# OnOff.net
KiCad netlist of a schematic drawn in EAGLE
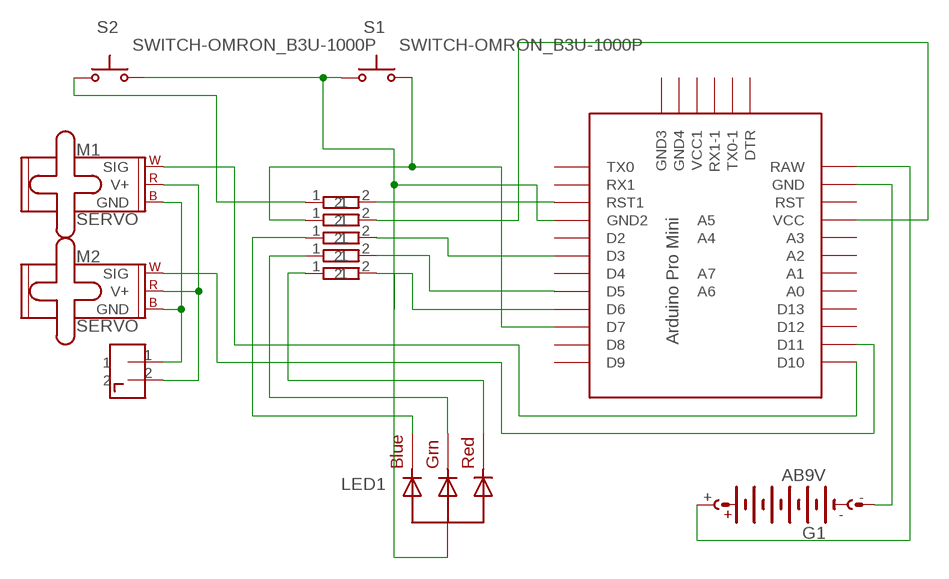
[diagram p0: schematic, sheet 1]

(export (version "E")
  (design (tool "Eeschema 10.0.6"))
  (components
    (comp (ref "CONNECTOR1")
      (value "2PIN")
      (footprint "eagle-import:2PIN")
      (libsource (lib "eagle-import") (part "2PIN"))
    )
    (comp (ref "CONNECTOR2")
      (value "RESISTER")
      (footprint "eagle-import:RESISTER_SOCKET")
      (libsource (lib "eagle-import") (part "RESISTER"))
    )
    (comp (ref "CONNECTOR3")
      (value "RESISTER")
      (footprint "eagle-import:RESISTER_SOCKET")
      (libsource (lib "eagle-import") (part "RESISTER"))
    )
    (comp (ref "CONNECTOR4")
      (value "RESISTER")
      (footprint "eagle-import:RESISTER_SOCKET")
      (libsource (lib "eagle-import") (part "RESISTER"))
    )
    (comp (ref "CONNECTOR5")
      (value "RESISTER")
      (footprint "eagle-import:RESISTER_SOCKET")
      (libsource (lib "eagle-import") (part "RESISTER"))
    )
    (comp (ref "CONNECTOR6")
      (value "RESISTER")
      (footprint "eagle-import:RESISTER_SOCKET")
      (libsource (lib "eagle-import") (part "RESISTER"))
    )
    (comp (ref "G1")
      (value "AB9V")
      (footprint "eagle-import:AB9V")
      (libsource (lib "eagle-import") (part "AB9V"))
    )
    (comp (ref "LED1")
      (value "RGBLED_CA-5MM")
      (footprint "eagle-import:LED5MMRGB")
      (libsource (lib "eagle-import") (part "RGBLED_CA-5MM"))
    )
    (comp (ref "M1")
      (value "SERVO")
      (footprint "eagle-import:1X03")
      (libsource (lib "eagle-import") (part "SERVO"))
    )
    (comp (ref "M2")
      (value "SERVO")
      (footprint "eagle-import:1X03")
      (libsource (lib "eagle-import") (part "SERVO"))
    )
    (comp (ref "S1")
      (value "SWITCH-OMRON_B3U-1000P")
      (footprint "eagle-import:SWITCH-OMRON_B3U-1000P")
      (libsource (lib "eagle-import") (part "SWITCH-OMRON_B3U-1000P"))
    )
    (comp (ref "S2")
      (value "SWITCH-OMRON_B3U-1000P")
      (footprint "eagle-import:SWITCH-OMRON_B3U-1000P")
      (libsource (lib "eagle-import") (part "SWITCH-OMRON_B3U-1000P"))
    )
    (comp (ref "U$1")
      (value "PRO-MINI-2")
      (footprint "eagle-import:PRO-MINI-2")
      (libsource (lib "eagle-import") (part "PRO-MINI-2"))
    )
  )
  (nets
    (net (code "1") (name "Net-(CONNECTOR2-Pad2)") (class "Default")
      (node (ref "CONNECTOR2") (pin "2") (pinfunction "2_2") (pintype "bidirectional"))
      (node (ref "U$1") (pin "RST1") (pinfunction "RST1_RST1") (pintype "bidirectional"))
    )
    (net (code "2") (name "Net-(CONNECTOR3-Pad2)") (class "Default")
      (node (ref "CONNECTOR3") (pin "2") (pinfunction "2_2") (pintype "bidirectional"))
      (node (ref "U$1") (pin "VCC") (pinfunction "VCC_VCC") (pintype "bidirectional"))
    )
    (net (code "3") (name "Net-(CONNECTOR4-Pad2)") (class "Default")
      (node (ref "CONNECTOR4") (pin "2") (pinfunction "2_2") (pintype "bidirectional"))
      (node (ref "U$1") (pin "D3") (pinfunction "D3_D3") (pintype "bidirectional"))
    )
    (net (code "4") (name "Net-(CONNECTOR5-Pad2)") (class "Default")
      (node (ref "CONNECTOR5") (pin "2") (pinfunction "2_2") (pintype "bidirectional"))
      (node (ref "U$1") (pin "D5") (pinfunction "D5_D5") (pintype "bidirectional"))
    )
    (net (code "5") (name "Net-(CONNECTOR6-Pad2)") (class "Default")
      (node (ref "CONNECTOR6") (pin "2") (pinfunction "2_2") (pintype "bidirectional"))
      (node (ref "U$1") (pin "D6") (pinfunction "D6_D6") (pintype "bidirectional"))
    )
    (net (code "6") (name "Net-(G1-Pad+)") (class "Default")
      (node (ref "G1") (pin "+") (pinfunction "+_+") (pintype "passive"))
      (node (ref "U$1") (pin "RAW") (pinfunction "RAW_RAW") (pintype "bidirectional"))
    )
    (net (code "7") (name "Net-(G1-Pad-)") (class "Default")
      (node (ref "G1") (pin "-") (pinfunction "-_-") (pintype "passive"))
      (node (ref "U$1") (pin "GND") (pinfunction "GND_GND") (pintype "bidirectional"))
    )
    (net (code "8") (name "Net-(LED1-BLUE)") (class "Default")
      (node (ref "CONNECTOR4") (pin "1") (pinfunction "1_1") (pintype "bidirectional"))
      (node (ref "LED1") (pin "4") (pinfunction "BLUE_4") (pintype "bidirectional"))
    )
    (net (code "9") (name "Net-(LED1-GREEN)") (class "Default")
      (node (ref "CONNECTOR5") (pin "1") (pinfunction "1_1") (pintype "bidirectional"))
      (node (ref "LED1") (pin "3") (pinfunction "GREEN_3") (pintype "bidirectional"))
    )
    (net (code "10") (name "Net-(LED1-RED)") (class "Default")
      (node (ref "CONNECTOR6") (pin "1") (pinfunction "1_1") (pintype "bidirectional"))
      (node (ref "LED1") (pin "1") (pinfunction "RED_1") (pintype "bidirectional"))
    )
    (net (code "11") (name "Net-(LED1-VCC)") (class "Default")
      (node (ref "LED1") (pin "2") (pinfunction "VCC_2") (pintype "bidirectional"))
      (node (ref "S1") (pin "1") (pinfunction "P_1") (pintype "passive"))
      (node (ref "S2") (pin "2") (pinfunction "S_2") (pintype "passive"))
      (node (ref "U$1") (pin "GND1") (pinfunction "GND2_GND1") (pintype "bidirectional"))
    )
    (net (code "12") (name "Net-(M1-GND)") (class "Default")
      (node (ref "CONNECTOR1") (pin "1") (pinfunction "1_1") (pintype "bidirectional"))
      (node (ref "M1") (pin "3") (pinfunction "GND_3") (pintype "bidirectional"))
      (node (ref "M2") (pin "3") (pinfunction "GND_3") (pintype "bidirectional"))
    )
    (net (code "13") (name "Net-(M1-SIG)") (class "Default")
      (node (ref "M1") (pin "1") (pinfunction "SIG_1") (pintype "bidirectional"))
      (node (ref "U$1") (pin "D10") (pinfunction "D10_D10") (pintype "bidirectional"))
    )
    (net (code "14") (name "Net-(M1-V+)") (class "Default")
      (node (ref "CONNECTOR1") (pin "2") (pinfunction "2_2") (pintype "bidirectional"))
      (node (ref "M1") (pin "2") (pinfunction "V+_2") (pintype "bidirectional"))
      (node (ref "M2") (pin "2") (pinfunction "V+_2") (pintype "bidirectional"))
    )
    (net (code "15") (name "Net-(M2-SIG)") (class "Default")
      (node (ref "M2") (pin "1") (pinfunction "SIG_1") (pintype "bidirectional"))
      (node (ref "U$1") (pin "D11") (pinfunction "D11_D11") (pintype "bidirectional"))
    )
    (net (code "16") (name "Net-(S1-S)") (class "Default")
      (node (ref "CONNECTOR3") (pin "1") (pinfunction "1_1") (pintype "bidirectional"))
      (node (ref "S1") (pin "2") (pinfunction "S_2") (pintype "passive"))
      (node (ref "U$1") (pin "D7") (pinfunction "D7_D7") (pintype "bidirectional"))
    )
    (net (code "17") (name "Net-(S2-P)") (class "Default")
      (node (ref "CONNECTOR2") (pin "1") (pinfunction "1_1") (pintype "bidirectional"))
      (node (ref "S2") (pin "1") (pinfunction "P_1") (pintype "passive"))
    )
    (net (code "18") (name "unconnected-(U$1-GND3-PadGND2)") (class "Default")
      (node (ref "U$1") (pin "GND2") (pinfunction "GND3_GND2") (pintype "bidirectional"))
    )
    (net (code "19") (name "unconnected-(U$1-GND4-PadGND3)") (class "Default")
      (node (ref "U$1") (pin "GND3") (pinfunction "GND4_GND3") (pintype "bidirectional"))
    )
    (net (code "20") (name "unconnected-(U$1-PadA0)") (class "Default")
      (node (ref "U$1") (pin "A0") (pinfunction "A0_A0") (pintype "bidirectional"))
    )
    (net (code "21") (name "unconnected-(U$1-PadA1)") (class "Default")
      (node (ref "U$1") (pin "A1") (pinfunction "A1_A1") (pintype "bidirectional"))
    )
    (net (code "22") (name "unconnected-(U$1-PadA2)") (class "Default")
      (node (ref "U$1") (pin "A2") (pinfunction "A2_A2") (pintype "bidirectional"))
    )
    (net (code "23") (name "unconnected-(U$1-PadA3)") (class "Default")
      (node (ref "U$1") (pin "A3") (pinfunction "A3_A3") (pintype "bidirectional"))
    )
    (net (code "24") (name "unconnected-(U$1-PadA4)") (class "Default")
      (node (ref "U$1") (pin "A4") (pinfunction "A4_A4") (pintype "bidirectional"))
    )
    (net (code "25") (name "unconnected-(U$1-PadA5)") (class "Default")
      (node (ref "U$1") (pin "A5") (pinfunction "A5_A5") (pintype "bidirectional"))
    )
    (net (code "26") (name "unconnected-(U$1-PadA6)") (class "Default")
      (node (ref "U$1") (pin "A6") (pinfunction "A6_A6") (pintype "bidirectional"))
    )
    (net (code "27") (name "unconnected-(U$1-PadA7)") (class "Default")
      (node (ref "U$1") (pin "A7") (pinfunction "A7_A7") (pintype "bidirectional"))
    )
    (net (code "28") (name "unconnected-(U$1-PadD2)") (class "Default")
      (node (ref "U$1") (pin "D2") (pinfunction "D2_D2") (pintype "bidirectional"))
    )
    (net (code "29") (name "unconnected-(U$1-PadD4)") (class "Default")
      (node (ref "U$1") (pin "D4") (pinfunction "D4_D4") (pintype "bidirectional"))
    )
    (net (code "30") (name "unconnected-(U$1-PadD8)") (class "Default")
      (node (ref "U$1") (pin "D8") (pinfunction "D8_D8") (pintype "bidirectional"))
    )
    (net (code "31") (name "unconnected-(U$1-PadD9)") (class "Default")
      (node (ref "U$1") (pin "D9") (pinfunction "D9_D9") (pintype "bidirectional"))
    )
    (net (code "32") (name "unconnected-(U$1-PadD12)") (class "Default")
      (node (ref "U$1") (pin "D12") (pinfunction "D12_D12") (pintype "bidirectional"))
    )
    (net (code "33") (name "unconnected-(U$1-PadD13)") (class "Default")
      (node (ref "U$1") (pin "D13") (pinfunction "D13_D13") (pintype "bidirectional"))
    )
    (net (code "34") (name "unconnected-(U$1-PadDTR)") (class "Default")
      (node (ref "U$1") (pin "DTR") (pinfunction "DTR_DTR") (pintype "bidirectional"))
    )
    (net (code "35") (name "unconnected-(U$1-PadRST)") (class "Default")
      (node (ref "U$1") (pin "RST") (pinfunction "RST_RST") (pintype "bidirectional"))
    )
    (net (code "36") (name "unconnected-(U$1-PadRX1)") (class "Default")
      (node (ref "U$1") (pin "RX1") (pinfunction "RX1_RX1") (pintype "bidirectional"))
    )
    (net (code "37") (name "unconnected-(U$1-PadRX1-1)") (class "Default")
      (node (ref "U$1") (pin "RX1-1") (pinfunction "RX1-1_RX1-1") (pintype "bidirectional"))
    )
    (net (code "38") (name "unconnected-(U$1-PadTX0)") (class "Default")
      (node (ref "U$1") (pin "TX0") (pinfunction "TX0_TX0") (pintype "bidirectional"))
    )
    (net (code "39") (name "unconnected-(U$1-PadTX0-1)") (class "Default")
      (node (ref "U$1") (pin "TX0-1") (pinfunction "TX0-1_TX0-1") (pintype "bidirectional"))
    )
    (net (code "40") (name "unconnected-(U$1-PadVCC1)") (class "Default")
      (node (ref "U$1") (pin "VCC1") (pinfunction "VCC1_VCC1") (pintype "bidirectional"))
    )
  )
)
